# dropweight_test_v6.net
KiCad netlist of a schematic drawn in EAGLE
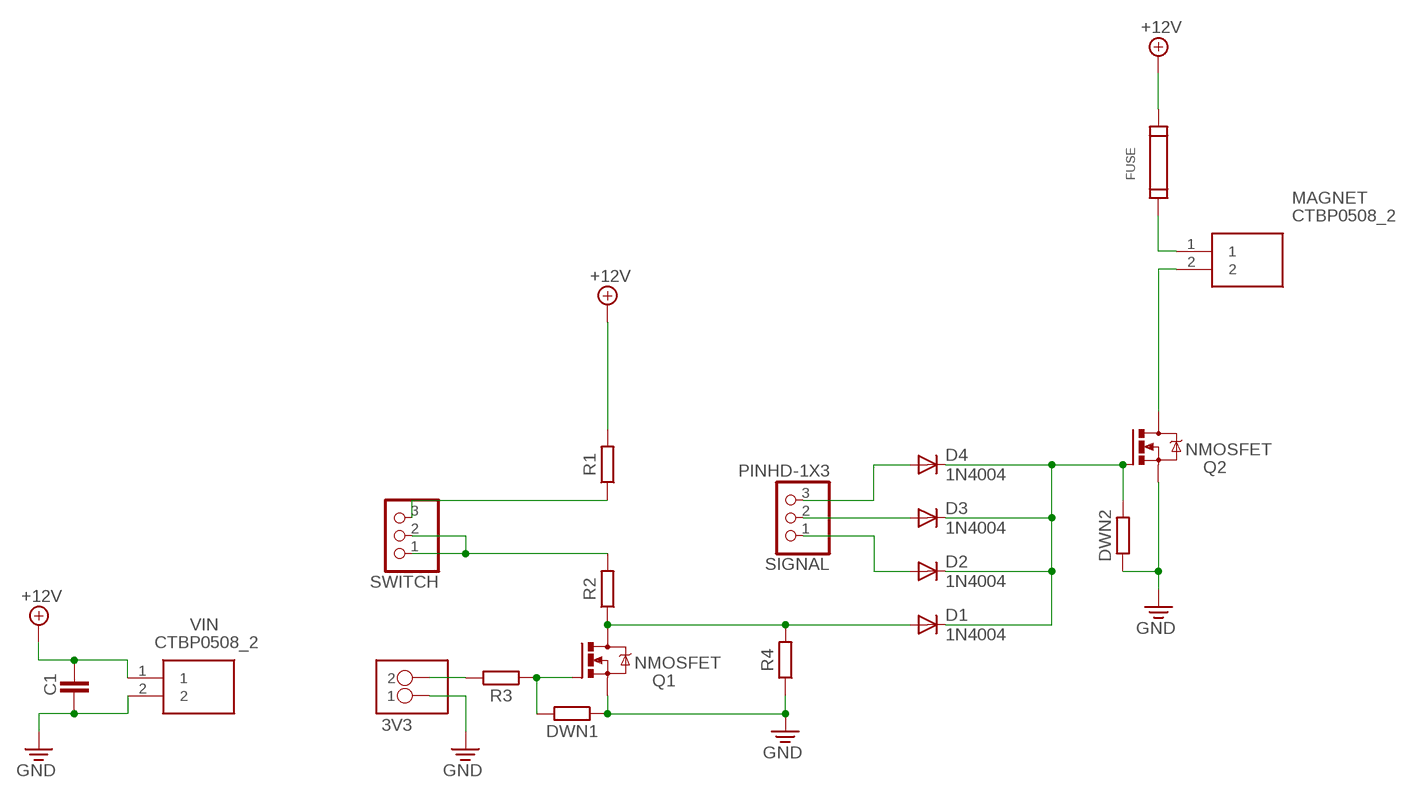
[diagram p0: schematic, sheet 1]

(export (version "E")
  (design (tool "Eeschema 10.0.6"))
  (components
    (comp (ref "3V3")
      (value "PINHD-1X02_1X02M")
      (footprint "eagle-import:1X02")
      (libsource (lib "eagle-import") (part "PINHD-1X02_1X02M"))
    )
    (comp (ref "C1")
      (value "CAPACITORCERAMIC-2.54MM")
      (footprint "eagle-import:CAP-THRU-2.54MM")
      (libsource (lib "eagle-import") (part "CAPACITORCERAMIC-2.54MM"))
    )
    (comp (ref "D1")
      (value "1N4004")
      (footprint "eagle-import:DO41-10")
      (libsource (lib "eagle-import") (part "1N4004"))
    )
    (comp (ref "D2")
      (value "1N4004")
      (footprint "eagle-import:DO41-10")
      (libsource (lib "eagle-import") (part "1N4004"))
    )
    (comp (ref "D3")
      (value "1N4004")
      (footprint "eagle-import:DO41-10")
      (libsource (lib "eagle-import") (part "1N4004"))
    )
    (comp (ref "D4")
      (value "1N4004")
      (footprint "eagle-import:DO41-10")
      (libsource (lib "eagle-import") (part "1N4004"))
    )
    (comp (ref "DWN1")
      (value "RESISTOR-BACKUP_AXIAL-10.16MM-PITCH")
      (footprint "eagle-import:RESAD1016W63L850D250B")
      (libsource (lib "eagle-import") (part "RESISTOR-BACKUP_AXIAL-10.16MM-PITCH"))
    )
    (comp (ref "DWN2")
      (value "RESISTOR-BACKUP_AXIAL-10.16MM-PITCH")
      (footprint "eagle-import:RESAD1016W63L850D250B")
      (libsource (lib "eagle-import") (part "RESISTOR-BACKUP_AXIAL-10.16MM-PITCH"))
    )
    (comp (ref "FUSE")
      (value "696108003002")
      (footprint "eagle-import:696108003002")
      (libsource (lib "eagle-import") (part "696108003002"))
    )
    (comp (ref "MAGNET")
      (value "CTBP0508_2")
      (footprint "eagle-import:CTBP05082")
      (fields (field (name "MANUFACTURER_PART_NUMBER") "CTBP0508/2"))
      (libsource (lib "eagle-import") (part "CTBP0508_2"))
    )
    (comp (ref "Q1")
      (value "NMOSFET")
      (footprint "eagle-import:TO220BV")
      (libsource (lib "eagle-import") (part "NMOSFET_TO220_"))
    )
    (comp (ref "Q2")
      (value "NMOSFET")
      (footprint "eagle-import:TO220BV")
      (libsource (lib "eagle-import") (part "NMOSFET_TO220_"))
    )
    (comp (ref "R1")
      (value "RESISTOR-BACKUP_AXIAL-10.16MM-PITCH")
      (footprint "eagle-import:RESAD1016W63L850D250B")
      (libsource (lib "eagle-import") (part "RESISTOR-BACKUP_AXIAL-10.16MM-PITCH"))
    )
    (comp (ref "R2")
      (value "RESISTOR-BACKUP_AXIAL-10.16MM-PITCH")
      (footprint "eagle-import:RESAD1016W63L850D250B")
      (libsource (lib "eagle-import") (part "RESISTOR-BACKUP_AXIAL-10.16MM-PITCH"))
    )
    (comp (ref "R3")
      (value "RESISTOR-BACKUP_AXIAL-10.16MM-PITCH")
      (footprint "eagle-import:RESAD1016W63L850D250B")
      (libsource (lib "eagle-import") (part "RESISTOR-BACKUP_AXIAL-10.16MM-PITCH"))
    )
    (comp (ref "R4")
      (value "RESISTOR-BACKUP_AXIAL-10.16MM-PITCH")
      (footprint "eagle-import:RESAD1016W63L850D250B")
      (libsource (lib "eagle-import") (part "RESISTOR-BACKUP_AXIAL-10.16MM-PITCH"))
    )
    (comp (ref "SIGNAL")
      (value "PINHD-1X3")
      (footprint "eagle-import:1X03")
      (fields (field (name "MANUFACTURER") "Generic"))
      (libsource (lib "eagle-import") (part "Connector_16378166_PINHD-1X3"))
    )
    (comp (ref "SWITCH")
      (value "PINHD-1X3")
      (footprint "eagle-import:1X03")
      (libsource (lib "eagle-import") (part "PINHD-1X3"))
    )
    (comp (ref "VIN")
      (value "CTBP0508_2")
      (footprint "eagle-import:CTBP05082")
      (fields (field (name "MANUFACTURER_PART_NUMBER") "CTBP0508/2"))
      (libsource (lib "eagle-import") (part "CTBP0508_2"))
    )
  )
  (nets
    (net (code "1") (name "+12V") (class "Default")
      (node (ref "C1") (pin "1") (pinfunction "1_1") (pintype "passive"))
      (node (ref "FUSE") (pin "2") (pinfunction "2_2") (pintype "passive"))
      (node (ref "R1") (pin "2") (pinfunction "2_2") (pintype "passive"))
      (node (ref "VIN") (pin "1") (pinfunction "1_1") (pintype "bidirectional"))
    )
    (net (code "2") (name "GND") (class "Default")
      (node (ref "3V3") (pin "1") (pinfunction "1_1") (pintype "bidirectional"))
      (node (ref "C1") (pin "2") (pinfunction "2_2") (pintype "passive"))
      (node (ref "DWN1") (pin "1") (pinfunction "1_1") (pintype "passive"))
      (node (ref "DWN2") (pin "1") (pinfunction "1_1") (pintype "passive"))
      (node (ref "Q1") (pin "S") (pinfunction "S_S") (pintype "passive"))
      (node (ref "Q2") (pin "S") (pinfunction "S_S") (pintype "passive"))
      (node (ref "R4") (pin "1") (pinfunction "1_1") (pintype "passive"))
      (node (ref "VIN") (pin "2") (pinfunction "2_2") (pintype "bidirectional"))
    )
    (net (code "3") (name "Net-(3V3-Pad2)") (class "Default")
      (node (ref "3V3") (pin "2") (pinfunction "2_2") (pintype "bidirectional"))
      (node (ref "R3") (pin "2") (pinfunction "2_2") (pintype "passive"))
    )
    (net (code "4") (name "Net-(D1-PadA)") (class "Default")
      (node (ref "D1") (pin "A") (pinfunction "A_A") (pintype "passive"))
      (node (ref "Q1") (pin "D") (pinfunction "D_D") (pintype "passive"))
      (node (ref "R2") (pin "1") (pinfunction "1_1") (pintype "passive"))
      (node (ref "R4") (pin "2") (pinfunction "2_2") (pintype "passive"))
    )
    (net (code "5") (name "Net-(D1-PadC)") (class "Default")
      (node (ref "D1") (pin "C") (pinfunction "C_C") (pintype "passive"))
      (node (ref "D2") (pin "C") (pinfunction "C_C") (pintype "passive"))
      (node (ref "D3") (pin "C") (pinfunction "C_C") (pintype "passive"))
      (node (ref "D4") (pin "C") (pinfunction "C_C") (pintype "passive"))
      (node (ref "DWN2") (pin "2") (pinfunction "2_2") (pintype "passive"))
      (node (ref "Q2") (pin "G") (pinfunction "G_G") (pintype "passive"))
    )
    (net (code "6") (name "Net-(D2-PadA)") (class "Default")
      (node (ref "D2") (pin "A") (pinfunction "A_A") (pintype "passive"))
      (node (ref "SIGNAL") (pin "1") (pinfunction "1_1") (pintype "passive"))
    )
    (net (code "7") (name "Net-(D3-PadA)") (class "Default")
      (node (ref "D3") (pin "A") (pinfunction "A_A") (pintype "passive"))
      (node (ref "SIGNAL") (pin "2") (pinfunction "2_2") (pintype "passive"))
    )
    (net (code "8") (name "Net-(D4-PadA)") (class "Default")
      (node (ref "D4") (pin "A") (pinfunction "A_A") (pintype "passive"))
      (node (ref "SIGNAL") (pin "3") (pinfunction "3_3") (pintype "passive"))
    )
    (net (code "9") (name "Net-(DWN1-Pad2)") (class "Default")
      (node (ref "DWN1") (pin "2") (pinfunction "2_2") (pintype "passive"))
      (node (ref "Q1") (pin "G") (pinfunction "G_G") (pintype "passive"))
      (node (ref "R3") (pin "1") (pinfunction "1_1") (pintype "passive"))
    )
    (net (code "10") (name "Net-(FUSE-Pad1)") (class "Default")
      (node (ref "FUSE") (pin "1") (pinfunction "1_1") (pintype "passive"))
      (node (ref "MAGNET") (pin "1") (pinfunction "1_1") (pintype "bidirectional"))
    )
    (net (code "11") (name "Net-(MAGNET-Pad2)") (class "Default")
      (node (ref "MAGNET") (pin "2") (pinfunction "2_2") (pintype "bidirectional"))
      (node (ref "Q2") (pin "D") (pinfunction "D_D") (pintype "passive"))
    )
    (net (code "12") (name "Net-(R1-Pad1)") (class "Default")
      (node (ref "R1") (pin "1") (pinfunction "1_1") (pintype "passive"))
      (node (ref "SWITCH") (pin "3") (pinfunction "3_3") (pintype "passive"))
    )
    (net (code "13") (name "Net-(R2-Pad2)") (class "Default")
      (node (ref "R2") (pin "2") (pinfunction "2_2") (pintype "passive"))
      (node (ref "SWITCH") (pin "1") (pinfunction "1_1") (pintype "passive"))
      (node (ref "SWITCH") (pin "2") (pinfunction "2_2") (pintype "passive"))
    )
  )
)
